# rx.net
KiCad netlist of a schematic drawn in EAGLE
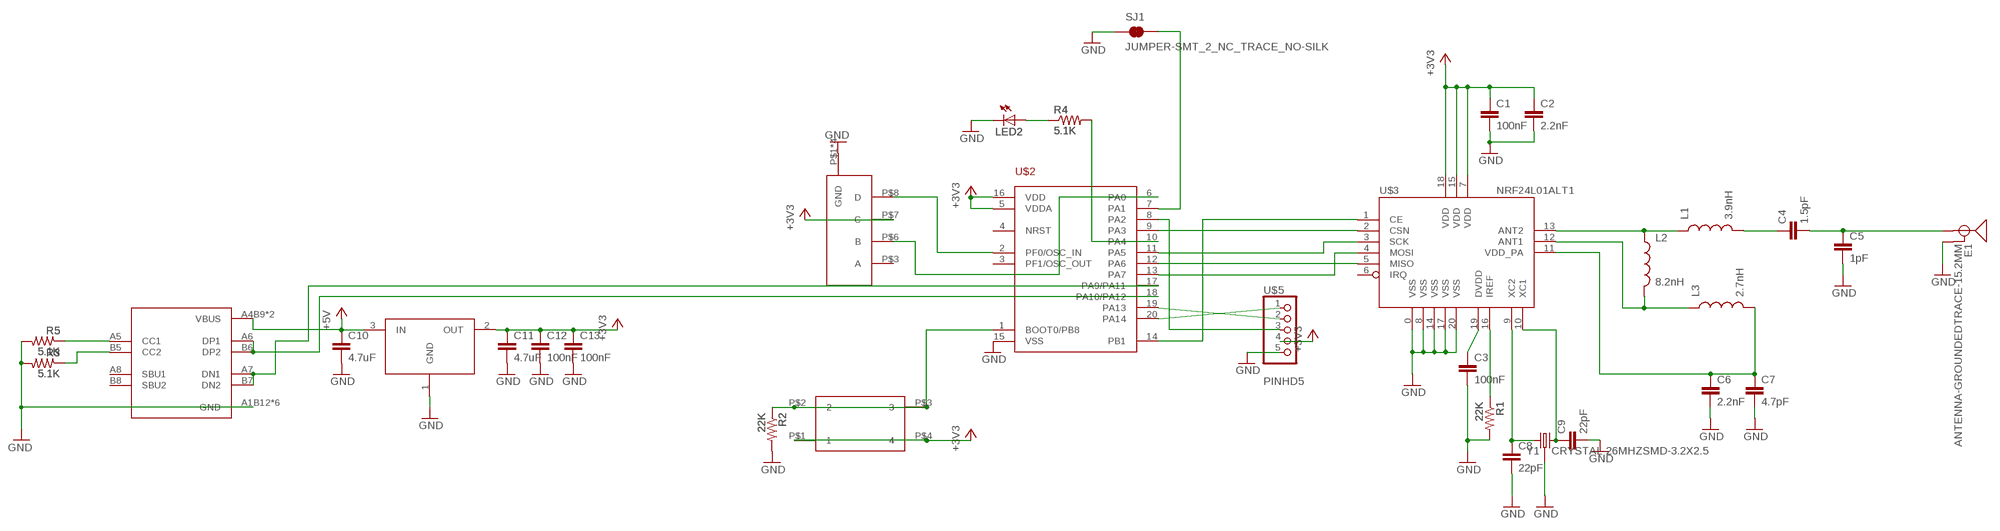
[diagram p0: schematic, sheet 1]

(export (version "E")
  (design (tool "Eeschema 10.0.6"))
  (components
    (comp (ref "C1")
      (value "100nF")
      (footprint "eagle-import:0805")
      (libsource (lib "eagle-import") (part "CAP0805"))
    )
    (comp (ref "C2")
      (value "2.2nF")
      (footprint "eagle-import:0805")
      (libsource (lib "eagle-import") (part "CAP0805"))
    )
    (comp (ref "C3")
      (value "100nF")
      (footprint "eagle-import:0805")
      (libsource (lib "eagle-import") (part "CAP0805"))
    )
    (comp (ref "C4")
      (value "1.5pF")
      (footprint "eagle-import:0805")
      (libsource (lib "eagle-import") (part "CAP0805"))
    )
    (comp (ref "C5")
      (value "1pF")
      (footprint "eagle-import:0805")
      (libsource (lib "eagle-import") (part "CAP0805"))
    )
    (comp (ref "C6")
      (value "2.2nF")
      (footprint "eagle-import:0805")
      (libsource (lib "eagle-import") (part "CAP0805"))
    )
    (comp (ref "C7")
      (value "4.7pF")
      (footprint "eagle-import:0805")
      (libsource (lib "eagle-import") (part "CAP0805"))
    )
    (comp (ref "C8")
      (value "22pF")
      (footprint "eagle-import:0805")
      (libsource (lib "eagle-import") (part "CAP0805"))
    )
    (comp (ref "C9")
      (value "22pF")
      (footprint "eagle-import:0805")
      (libsource (lib "eagle-import") (part "CAP0805"))
    )
    (comp (ref "C10")
      (value "4.7uF")
      (footprint "eagle-import:0805")
      (libsource (lib "eagle-import") (part "CAP0805"))
    )
    (comp (ref "C11")
      (value "4.7uF")
      (footprint "eagle-import:0805")
      (libsource (lib "eagle-import") (part "CAP0805"))
    )
    (comp (ref "C12")
      (value "100nF")
      (footprint "eagle-import:0805")
      (libsource (lib "eagle-import") (part "CAP0805"))
    )
    (comp (ref "C13")
      (value "100nF")
      (footprint "eagle-import:0805")
      (libsource (lib "eagle-import") (part "CAP0805"))
    )
    (comp (ref "E1")
      (value "ANTENNA-GROUNDEDTRACE-15.2MM")
      (footprint "eagle-import:TRACE_ANTENNA_2.4GHZ_15.2MM")
      (libsource (lib "eagle-import") (part "ANTENNA-GROUNDEDTRACE-15.2MM"))
    )
    (comp (ref "L1")
      (value "3.9nH")
      (footprint "eagle-import:0805")
      (libsource (lib "eagle-import") (part "INDUCTOR0805"))
    )
    (comp (ref "L2")
      (value "8.2nH")
      (footprint "eagle-import:0805")
      (libsource (lib "eagle-import") (part "INDUCTOR0805"))
    )
    (comp (ref "L3")
      (value "2.7nH")
      (footprint "eagle-import:0805")
      (libsource (lib "eagle-import") (part "INDUCTOR0805"))
    )
    (comp (ref "LED2")
      (value "LEDCHIP-LED0805")
      (footprint "eagle-import:CHIP-LED0805")
      (libsource (lib "eagle-import") (part "LEDCHIP-LED0805"))
    )
    (comp (ref "R1")
      (value "22K")
      (footprint "eagle-import:0805")
      (libsource (lib "eagle-import") (part "RESISTOR0805-RES"))
    )
    (comp (ref "R2")
      (value "22K")
      (footprint "eagle-import:0805")
      (libsource (lib "eagle-import") (part "RESISTOR0805-RES"))
    )
    (comp (ref "R3")
      (value "5.1K")
      (footprint "eagle-import:0805")
      (libsource (lib "eagle-import") (part "RESISTOR0805-RES"))
    )
    (comp (ref "R4")
      (value "5.1K")
      (footprint "eagle-import:0805")
      (libsource (lib "eagle-import") (part "RESISTOR0805-RES"))
    )
    (comp (ref "R5")
      (value "5.1K")
      (footprint "eagle-import:0805")
      (libsource (lib "eagle-import") (part "RESISTOR0805-RES"))
    )
    (comp (ref "SJ1")
      (value "JUMPER-SMT_2_NC_TRACE_NO-SILK")
      (footprint "eagle-import:SMT-JUMPER_2_NC_TRACE_NO-SILK")
      (libsource (lib "eagle-import") (part "JUMPER-SMT_2_NC_TRACE_NO-SILK"))
    )
    (comp (ref "U$1")
      (value "SW_3POS_DEVSW_3POS_OFFICIAL")
      (footprint "eagle-import:SW_3POS_FOOT_OFFICIAL")
      (libsource (lib "eagle-import") (part "SW_3POS_DEVSW_3POS_OFFICIAL"))
    )
    (comp (ref "U$2")
      (value "STM32F042F4")
      (footprint "eagle-import:TSSOP20")
      (libsource (lib "eagle-import") (part "STM32F042F4"))
    )
    (comp (ref "U$3")
      (value "NRF24L01ALT1")
      (footprint "eagle-import:QFN20_ALT1")
      (libsource (lib "eagle-import") (part "NRF24L01ALT1"))
    )
    (comp (ref "U$4")
      (value "XC6206_DEV")
      (footprint "eagle-import:SOT23R_INFINEON")
      (libsource (lib "eagle-import") (part "XC6206_DEV"))
    )
    (comp (ref "U$5")
      (value "PINHD5")
      (footprint "eagle-import:1X05")
      (libsource (lib "eagle-import") (part "PINHD5"))
    )
    (comp (ref "U$6")
      (value "USBC_16P")
      (footprint "eagle-import:USBC_16P_FOOT")
      (libsource (lib "eagle-import") (part "USBC_16P"))
    )
    (comp (ref "U$10")
      (value "324_SW324_SWITCH_FOOT_HOLE")
      (footprint "eagle-import:342_SWICH_FOOT_HOLE")
      (libsource (lib "eagle-import") (part "324_SW324_SWITCH_FOOT_HOLE"))
    )
    (comp (ref "Y1")
      (value "CRYSTAL-26MHZSMD-3.2X2.5")
      (footprint "eagle-import:CRYSTAL-SMD-3.2X2.5MM")
      (libsource (lib "eagle-import") (part "CRYSTAL-26MHZSMD-3.2X2.5"))
    )
  )
  (nets
    (net (code "1") (name "+3V3") (class "Default")
      (node (ref "C1") (pin "1") (pinfunction "1_1") (pintype "passive"))
      (node (ref "C11") (pin "1") (pinfunction "1_1") (pintype "passive"))
      (node (ref "C12") (pin "1") (pinfunction "1_1") (pintype "passive"))
      (node (ref "C13") (pin "1") (pinfunction "1_1") (pintype "passive"))
      (node (ref "C2") (pin "1") (pinfunction "1_1") (pintype "passive"))
      (node (ref "U$1") (pin "P$7") (pinfunction "C_P$7") (pintype "bidirectional"))
      (node (ref "U$10") (pin "P$1") (pinfunction "1_P$1") (pintype "bidirectional"))
      (node (ref "U$10") (pin "P$4") (pinfunction "4_P$4") (pintype "bidirectional"))
      (node (ref "U$2") (pin "16") (pinfunction "VDD_16") (pintype "bidirectional"))
      (node (ref "U$2") (pin "5") (pinfunction "VDDA_5") (pintype "bidirectional"))
      (node (ref "U$3") (pin "15") (pinfunction "VDD_15") (pintype "power_in"))
      (node (ref "U$3") (pin "18") (pinfunction "VDD_18") (pintype "power_in"))
      (node (ref "U$3") (pin "7") (pinfunction "VDD_7") (pintype "power_in"))
      (node (ref "U$4") (pin "2") (pinfunction "OUT_2") (pintype "bidirectional"))
      (node (ref "U$5") (pin "4") (pinfunction "4_4") (pintype "passive"))
    )
    (net (code "2") (name "+5V") (class "Default")
      (node (ref "C10") (pin "1") (pinfunction "1_1") (pintype "passive"))
      (node (ref "U$4") (pin "3") (pinfunction "IN_3") (pintype "bidirectional"))
      (node (ref "U$6") (pin "A4B9") (pinfunction "VBUS_A4B9") (pintype "bidirectional"))
      (node (ref "U$6") (pin "B4A9") (pinfunction "VBUS_B4A9") (pintype "bidirectional"))
    )
    (net (code "3") (name "GND") (class "Default")
      (node (ref "C1") (pin "2") (pinfunction "2_2") (pintype "passive"))
      (node (ref "C10") (pin "2") (pinfunction "2_2") (pintype "passive"))
      (node (ref "C11") (pin "2") (pinfunction "2_2") (pintype "passive"))
      (node (ref "C12") (pin "2") (pinfunction "2_2") (pintype "passive"))
      (node (ref "C13") (pin "2") (pinfunction "2_2") (pintype "passive"))
      (node (ref "C2") (pin "2") (pinfunction "2_2") (pintype "passive"))
      (node (ref "C3") (pin "2") (pinfunction "2_2") (pintype "passive"))
      (node (ref "C5") (pin "2") (pinfunction "2_2") (pintype "passive"))
      (node (ref "C6") (pin "2") (pinfunction "2_2") (pintype "passive"))
      (node (ref "C7") (pin "2") (pinfunction "2_2") (pintype "passive"))
      (node (ref "C8") (pin "2") (pinfunction "2_2") (pintype "passive"))
      (node (ref "C9") (pin "2") (pinfunction "2_2") (pintype "passive"))
      (node (ref "E1") (pin "GND") (pinfunction "GND_GND") (pintype "bidirectional"))
      (node (ref "LED2") (pin "C") (pinfunction "C_C") (pintype "passive"))
      (node (ref "R1") (pin "2") (pinfunction "2_2") (pintype "passive"))
      (node (ref "R2") (pin "2") (pinfunction "2_2") (pintype "passive"))
      (node (ref "R3") (pin "2") (pinfunction "2_2") (pintype "passive"))
      (node (ref "R5") (pin "2") (pinfunction "2_2") (pintype "passive"))
      (node (ref "SJ1") (pin "1") (pinfunction "1_1") (pintype "passive"))
      (node (ref "U$1") (pin "P$1") (pinfunction "GND_P$1") (pintype "bidirectional"))
      (node (ref "U$1") (pin "P$2") (pinfunction "GND_P$2") (pintype "bidirectional"))
      (node (ref "U$1") (pin "P$4") (pinfunction "GND_P$4") (pintype "bidirectional"))
      (node (ref "U$1") (pin "P$5") (pinfunction "GND_P$5") (pintype "bidirectional"))
      (node (ref "U$2") (pin "15") (pinfunction "VSS_15") (pintype "bidirectional"))
      (node (ref "U$3") (pin "0") (pinfunction "VSS_0") (pintype "power_in"))
      (node (ref "U$3") (pin "14") (pinfunction "VSS_14") (pintype "power_in"))
      (node (ref "U$3") (pin "17") (pinfunction "VSS_17") (pintype "power_in"))
      (node (ref "U$3") (pin "20") (pinfunction "VSS_20") (pintype "power_in"))
      (node (ref "U$3") (pin "8") (pinfunction "VSS_8") (pintype "power_in"))
      (node (ref "U$4") (pin "1") (pinfunction "GND_1") (pintype "bidirectional"))
      (node (ref "U$5") (pin "5") (pinfunction "5_5") (pintype "passive"))
      (node (ref "U$6") (pin "A1B12") (pinfunction "GND_A1B12") (pintype "bidirectional"))
      (node (ref "U$6") (pin "B11A12") (pinfunction "GND_B11A12") (pintype "bidirectional"))
      (node (ref "U$6") (pin "P$13") (pinfunction "GND_P$13") (pintype "bidirectional"))
      (node (ref "U$6") (pin "P$14") (pinfunction "GND_P$14") (pintype "bidirectional"))
      (node (ref "U$6") (pin "P$15") (pinfunction "GND_P$15") (pintype "bidirectional"))
      (node (ref "U$6") (pin "P$16") (pinfunction "GND_P$16") (pintype "bidirectional"))
      (node (ref "Y1") (pin "2") (pinfunction "3_2") (pintype "passive"))
      (node (ref "Y1") (pin "4") (pinfunction "3_4") (pintype "passive"))
    )
    (net (code "4") (name "Net-(C4-Pad1)") (class "Default")
      (node (ref "C4") (pin "1") (pinfunction "1_1") (pintype "passive"))
      (node (ref "L1") (pin "2") (pinfunction "2_2") (pintype "passive"))
    )
    (net (code "5") (name "Net-(E1-SIGNAL)") (class "Default")
      (node (ref "C4") (pin "2") (pinfunction "2_2") (pintype "passive"))
      (node (ref "C5") (pin "1") (pinfunction "1_1") (pintype "passive"))
      (node (ref "E1") (pin "ANT") (pinfunction "SIGNAL_ANT") (pintype "bidirectional"))
    )
    (net (code "6") (name "Net-(LED2-PadA)") (class "Default")
      (node (ref "LED2") (pin "A") (pinfunction "A_A") (pintype "passive"))
      (node (ref "R4") (pin "1") (pinfunction "1_1") (pintype "passive"))
    )
    (net (code "7") (name "Net-(U$1-B)") (class "Default")
      (node (ref "U$1") (pin "P$6") (pinfunction "B_P$6") (pintype "bidirectional"))
      (node (ref "U$2") (pin "6") (pinfunction "PA0_6") (pintype "bidirectional"))
    )
    (net (code "8") (name "Net-(U$1-D)") (class "Default")
      (node (ref "U$1") (pin "P$8") (pinfunction "D_P$8") (pintype "bidirectional"))
      (node (ref "U$2") (pin "2") (pinfunction "PF0/OSC_IN_2") (pintype "bidirectional"))
    )
    (net (code "9") (name "Net-(U$2-PA1)") (class "Default")
      (node (ref "SJ1") (pin "2") (pinfunction "2_2") (pintype "passive"))
      (node (ref "U$2") (pin "7") (pinfunction "PA1_7") (pintype "bidirectional"))
    )
    (net (code "10") (name "Net-(U$2-PA2)") (class "Default")
      (node (ref "U$2") (pin "8") (pinfunction "PA2_8") (pintype "bidirectional"))
      (node (ref "U$5") (pin "3") (pinfunction "3_3") (pintype "passive"))
    )
    (net (code "11") (name "Net-(U$2-PA3)") (class "Default")
      (node (ref "U$2") (pin "9") (pinfunction "PA3_9") (pintype "bidirectional"))
      (node (ref "U$3") (pin "2") (pinfunction "CSN_2") (pintype "input"))
    )
    (net (code "12") (name "Net-(U$2-PA4)") (class "Default")
      (node (ref "R4") (pin "2") (pinfunction "2_2") (pintype "passive"))
      (node (ref "U$2") (pin "10") (pinfunction "PA4_10") (pintype "bidirectional"))
    )
    (net (code "13") (name "Net-(U$2-PA5)") (class "Default")
      (node (ref "U$2") (pin "11") (pinfunction "PA5_11") (pintype "bidirectional"))
      (node (ref "U$3") (pin "3") (pinfunction "SCK_3") (pintype "input"))
    )
    (net (code "14") (name "Net-(U$2-PA6)") (class "Default")
      (node (ref "U$2") (pin "12") (pinfunction "PA6_12") (pintype "bidirectional"))
      (node (ref "U$3") (pin "5") (pinfunction "MISO_5") (pintype "output"))
    )
    (net (code "15") (name "Net-(U$2-PA7)") (class "Default")
      (node (ref "U$2") (pin "13") (pinfunction "PA7_13") (pintype "bidirectional"))
      (node (ref "U$3") (pin "4") (pinfunction "MOSI_4") (pintype "input"))
    )
    (net (code "16") (name "Net-(U$2-PA9{slash}PA11)") (class "Default")
      (node (ref "U$2") (pin "17") (pinfunction "PA9/PA11_17") (pintype "bidirectional"))
      (node (ref "U$6") (pin "A7") (pinfunction "DN1_A7") (pintype "bidirectional"))
      (node (ref "U$6") (pin "B7") (pinfunction "DN2_B7") (pintype "bidirectional"))
    )
    (net (code "17") (name "Net-(U$2-PA10{slash}PA12)") (class "Default")
      (node (ref "U$2") (pin "18") (pinfunction "PA10/PA12_18") (pintype "bidirectional"))
      (node (ref "U$6") (pin "A6") (pinfunction "DP1_A6") (pintype "bidirectional"))
      (node (ref "U$6") (pin "B6") (pinfunction "DP2_B6") (pintype "bidirectional"))
    )
    (net (code "18") (name "Net-(U$2-PA13)") (class "Default")
      (node (ref "U$2") (pin "19") (pinfunction "PA13_19") (pintype "bidirectional"))
      (node (ref "U$5") (pin "2") (pinfunction "2_2") (pintype "passive"))
    )
    (net (code "19") (name "Net-(U$2-PA14)") (class "Default")
      (node (ref "U$2") (pin "20") (pinfunction "PA14_20") (pintype "bidirectional"))
      (node (ref "U$5") (pin "1") (pinfunction "1_1") (pintype "passive"))
    )
    (net (code "20") (name "Net-(U$2-PB1)") (class "Default")
      (node (ref "U$2") (pin "14") (pinfunction "PB1_14") (pintype "bidirectional"))
      (node (ref "U$3") (pin "1") (pinfunction "CE_1") (pintype "input"))
    )
    (net (code "21") (name "Net-(U$3-ANT1)") (class "Default")
      (node (ref "L2") (pin "2") (pinfunction "2_2") (pintype "passive"))
      (node (ref "L3") (pin "1") (pinfunction "1_1") (pintype "passive"))
      (node (ref "U$3") (pin "12") (pinfunction "ANT1_12") (pintype "output"))
    )
    (net (code "22") (name "Net-(U$3-ANT2)") (class "Default")
      (node (ref "L1") (pin "1") (pinfunction "1_1") (pintype "passive"))
      (node (ref "L2") (pin "1") (pinfunction "1_1") (pintype "passive"))
      (node (ref "U$3") (pin "13") (pinfunction "ANT2_13") (pintype "output"))
    )
    (net (code "23") (name "Net-(U$3-DVDD)") (class "Default")
      (node (ref "C3") (pin "1") (pinfunction "1_1") (pintype "passive"))
      (node (ref "U$3") (pin "19") (pinfunction "DVDD_19") (pintype "power_in"))
    )
    (net (code "24") (name "Net-(U$3-IREF)") (class "Default")
      (node (ref "R1") (pin "1") (pinfunction "1_1") (pintype "passive"))
      (node (ref "U$3") (pin "16") (pinfunction "IREF_16") (pintype "input"))
    )
    (net (code "25") (name "Net-(U$3-VDD_PA)") (class "Default")
      (node (ref "C6") (pin "1") (pinfunction "1_1") (pintype "passive"))
      (node (ref "C7") (pin "1") (pinfunction "1_1") (pintype "passive"))
      (node (ref "L3") (pin "2") (pinfunction "2_2") (pintype "passive"))
      (node (ref "U$3") (pin "11") (pinfunction "VDD_PA_11") (pintype "power_in"))
    )
    (net (code "26") (name "Net-(U$3-XC1)") (class "Default")
      (node (ref "C9") (pin "1") (pinfunction "1_1") (pintype "passive"))
      (node (ref "U$3") (pin "10") (pinfunction "XC1_10") (pintype "input"))
      (node (ref "Y1") (pin "3") (pinfunction "2_3") (pintype "passive"))
    )
    (net (code "27") (name "Net-(U$3-XC2)") (class "Default")
      (node (ref "C8") (pin "1") (pinfunction "1_1") (pintype "passive"))
      (node (ref "U$3") (pin "9") (pinfunction "XC2_9") (pintype "input"))
      (node (ref "Y1") (pin "1") (pinfunction "1_1") (pintype "passive"))
    )
    (net (code "28") (name "Net-(U$6-CC1)") (class "Default")
      (node (ref "R5") (pin "1") (pinfunction "1_1") (pintype "passive"))
      (node (ref "U$6") (pin "A5") (pinfunction "CC1_A5") (pintype "bidirectional"))
    )
    (net (code "29") (name "Net-(U$6-CC2)") (class "Default")
      (node (ref "R3") (pin "1") (pinfunction "1_1") (pintype "passive"))
      (node (ref "U$6") (pin "B5") (pinfunction "CC2_B5") (pintype "bidirectional"))
    )
    (net (code "30") (name "Net-(U$10-2)") (class "Default")
      (node (ref "R2") (pin "1") (pinfunction "1_1") (pintype "passive"))
      (node (ref "U$10") (pin "P$2") (pinfunction "2_P$2") (pintype "bidirectional"))
      (node (ref "U$10") (pin "P$3") (pinfunction "3_P$3") (pintype "bidirectional"))
      (node (ref "U$2") (pin "1") (pinfunction "BOOT0/PB8_1") (pintype "bidirectional"))
    )
    (net (code "31") (name "unconnected-(U$1-A-PadP$3)") (class "Default")
      (node (ref "U$1") (pin "P$3") (pinfunction "A_P$3") (pintype "bidirectional"))
    )
    (net (code "32") (name "unconnected-(U$2-NRST-Pad4)") (class "Default")
      (node (ref "U$2") (pin "4") (pinfunction "NRST_4") (pintype "bidirectional"))
    )
    (net (code "33") (name "unconnected-(U$2-PF1{slash}OSC_OUT-Pad3)") (class "Default")
      (node (ref "U$2") (pin "3") (pinfunction "PF1/OSC_OUT_3") (pintype "bidirectional"))
    )
    (net (code "34") (name "unconnected-(U$3-IRQ-Pad6)") (class "Default")
      (node (ref "U$3") (pin "6") (pinfunction "IRQ_6") (pintype "output"))
    )
    (net (code "35") (name "unconnected-(U$6-SBU1-PadA8)") (class "Default")
      (node (ref "U$6") (pin "A8") (pinfunction "SBU1_A8") (pintype "bidirectional"))
    )
    (net (code "36") (name "unconnected-(U$6-SBU2-PadB8)") (class "Default")
      (node (ref "U$6") (pin "B8") (pinfunction "SBU2_B8") (pintype "bidirectional"))
    )
  )
)
